# POWER.net
KiCad netlist of a schematic drawn in Altium Designer
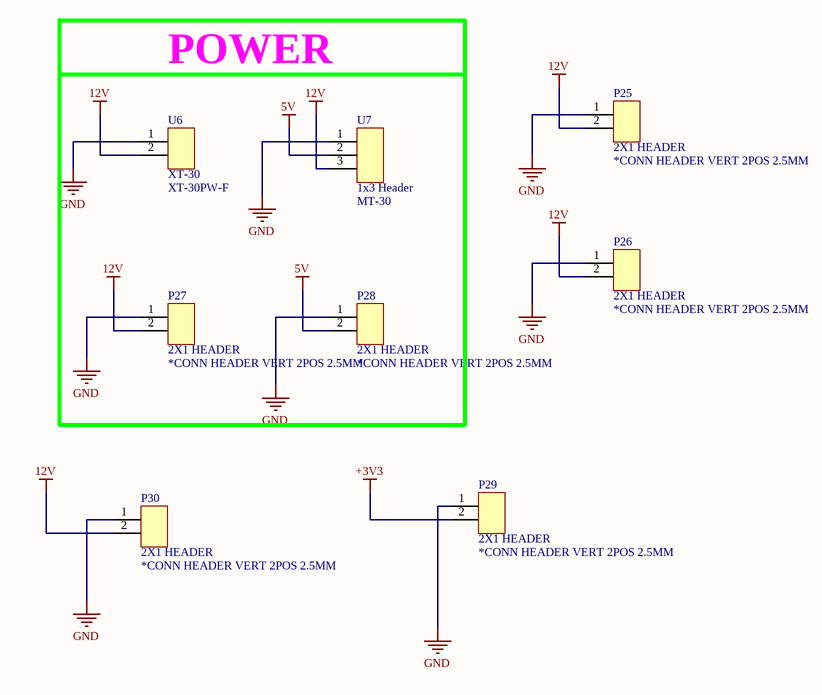
[diagram p0: POWER.SchDoc]

(export (version "E")
  (design (tool "Eeschema 10.0.6"))
  (components
    (comp (ref "P25")
      (value "*CONN HEADER VERT 2POS 2.5MM")
      (footprint "51025-02-0100-01")
      (description "Conn Shrouded Header (4 Sides) HDR 2 POS 2.5mm Solder ST Top Entry Thru-Hole Box")
      (fields
        (field (name "MANUFACTURER") "JST")
        (field (name "MANUFACTURER PART NUMBER") "B2B-XH-A(LF)(SN)")
      )
      (libsource (lib "Schlib1") (part "B2B-XH-AM(LF)(SN)"))
    )
    (comp (ref "P26")
      (value "*CONN HEADER VERT 2POS 2.5MM")
      (footprint "51025-02-0100-01")
      (description "Conn Shrouded Header (4 Sides) HDR 2 POS 2.5mm Solder ST Top Entry Thru-Hole Box")
      (fields
        (field (name "MANUFACTURER") "JST")
        (field (name "MANUFACTURER PART NUMBER") "B2B-XH-A(LF)(SN)")
      )
      (libsource (lib "Schlib1") (part "B2B-XH-AM(LF)(SN)"))
    )
    (comp (ref "P27")
      (value "*CONN HEADER VERT 2POS 2.5MM")
      (footprint "51025-02-0100-01")
      (description "Conn Shrouded Header (4 Sides) HDR 2 POS 2.5mm Solder ST Top Entry Thru-Hole Box")
      (fields
        (field (name "MANUFACTURER") "JST")
        (field (name "MANUFACTURER PART NUMBER") "B2B-XH-A(LF)(SN)")
      )
      (libsource (lib "Schlib1") (part "B2B-XH-AM(LF)(SN)"))
    )
    (comp (ref "P28")
      (value "*CONN HEADER VERT 2POS 2.5MM")
      (footprint "51025-02-0100-01")
      (description "Conn Shrouded Header (4 Sides) HDR 2 POS 2.5mm Solder ST Top Entry Thru-Hole Box")
      (fields
        (field (name "MANUFACTURER") "JST")
        (field (name "MANUFACTURER PART NUMBER") "B2B-XH-A(LF)(SN)")
      )
      (libsource (lib "Schlib1") (part "B2B-XH-AM(LF)(SN)"))
    )
    (comp (ref "P29")
      (value "*CONN HEADER VERT 2POS 2.5MM")
      (footprint "51025-02-0100-01")
      (description "Conn Shrouded Header (4 Sides) HDR 2 POS 2.5mm Solder ST Top Entry Thru-Hole Box")
      (fields
        (field (name "MANUFACTURER") "JST")
        (field (name "MANUFACTURER PART NUMBER") "B2B-XH-A(LF)(SN)")
      )
      (libsource (lib "Schlib1") (part "B2B-XH-AM(LF)(SN)"))
    )
    (comp (ref "P30")
      (value "*CONN HEADER VERT 2POS 2.5MM")
      (footprint "51025-02-0100-01")
      (description "Conn Shrouded Header (4 Sides) HDR 2 POS 2.5mm Solder ST Top Entry Thru-Hole Box")
      (fields
        (field (name "MANUFACTURER") "JST")
        (field (name "MANUFACTURER PART NUMBER") "B2B-XH-A(LF)(SN)")
      )
      (libsource (lib "Schlib1") (part "B2B-XH-AM(LF)(SN)"))
    )
    (comp (ref "U6")
      (value "XT-30PW-F")
      (footprint "XT-30PW-F")
      (libsource (lib "Schlib1") (part "XT-30PW-F"))
    )
    (comp (ref "U7") (value "MT-30") (footprint "MT-30") (libsource (lib "Schlib1") (part "MT-30")))
  )
  (nets
    (net (code "1") (name "+3V3") (class "Default") (node (ref "P29") (pin "2") (pintype "passive")))
    (net (code "2") (name "5V") (class "Default")
      (node (ref "P28") (pin "2") (pintype "passive"))
      (node (ref "U7") (pin "2") (pintype "passive"))
    )
    (net (code "3") (name "12V") (class "Default")
      (node (ref "P25") (pin "2") (pintype "passive"))
      (node (ref "P26") (pin "2") (pintype "passive"))
      (node (ref "P27") (pin "2") (pintype "passive"))
      (node (ref "P30") (pin "2") (pintype "passive"))
      (node (ref "U6") (pin "2") (pintype "passive"))
      (node (ref "U7") (pin "3") (pintype "passive"))
    )
    (net (code "4") (name "GND") (class "Default")
      (node (ref "P25") (pin "1") (pintype "passive"))
      (node (ref "P26") (pin "1") (pintype "passive"))
      (node (ref "P27") (pin "1") (pintype "passive"))
      (node (ref "P28") (pin "1") (pintype "passive"))
      (node (ref "P29") (pin "1") (pintype "passive"))
      (node (ref "P30") (pin "1") (pintype "passive"))
      (node (ref "U6") (pin "1") (pintype "passive"))
      (node (ref "U7") (pin "1") (pintype "passive"))
    )
  )
)
